# layer4.net
KiCad netlist of a schematic drawn in EAGLE
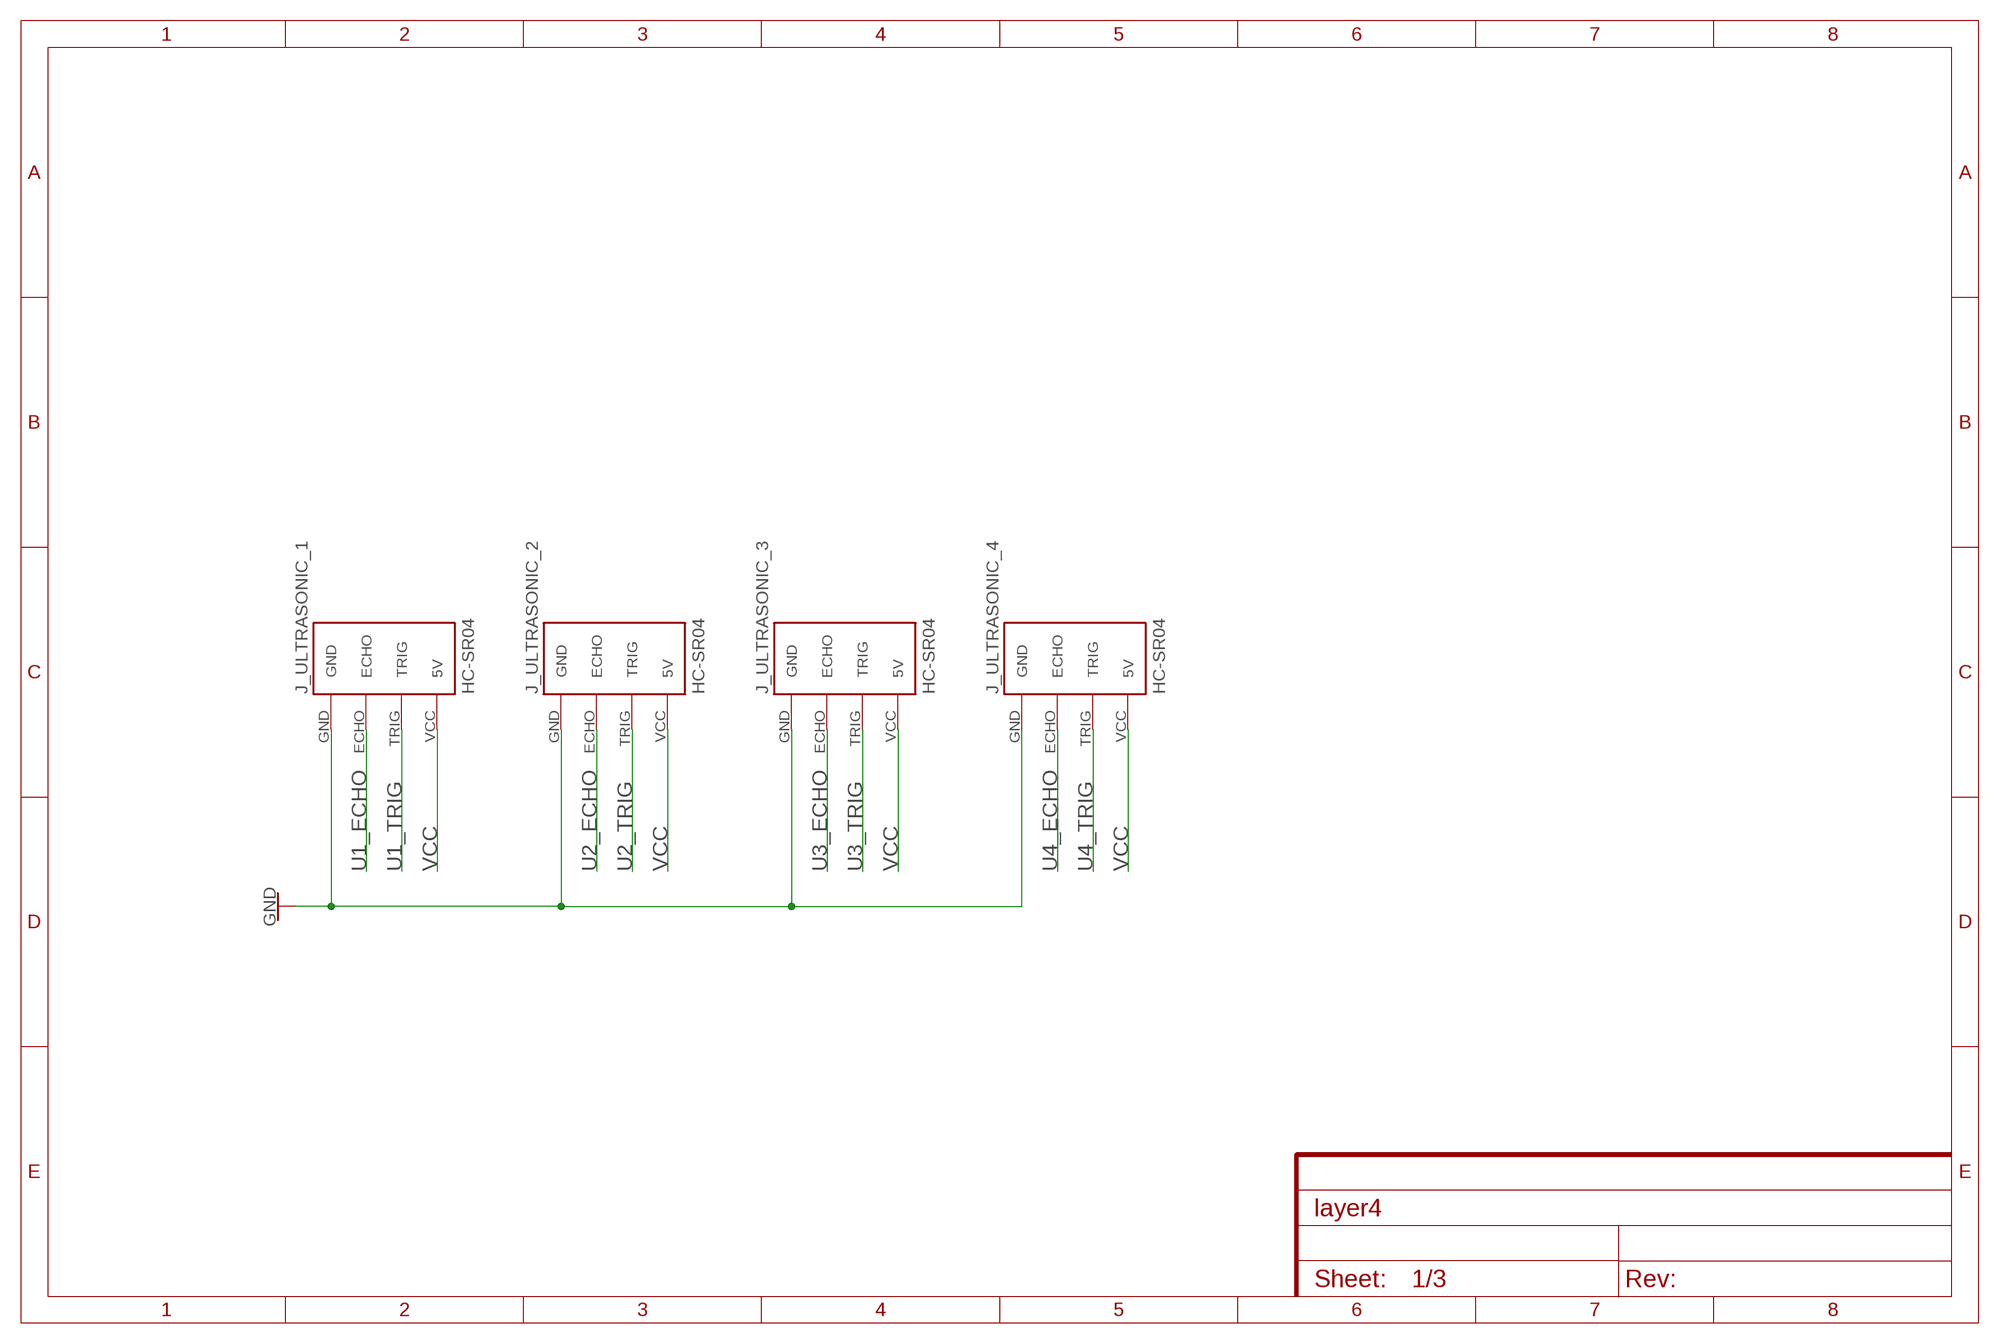
[diagram p0: schematic, sheet 1]
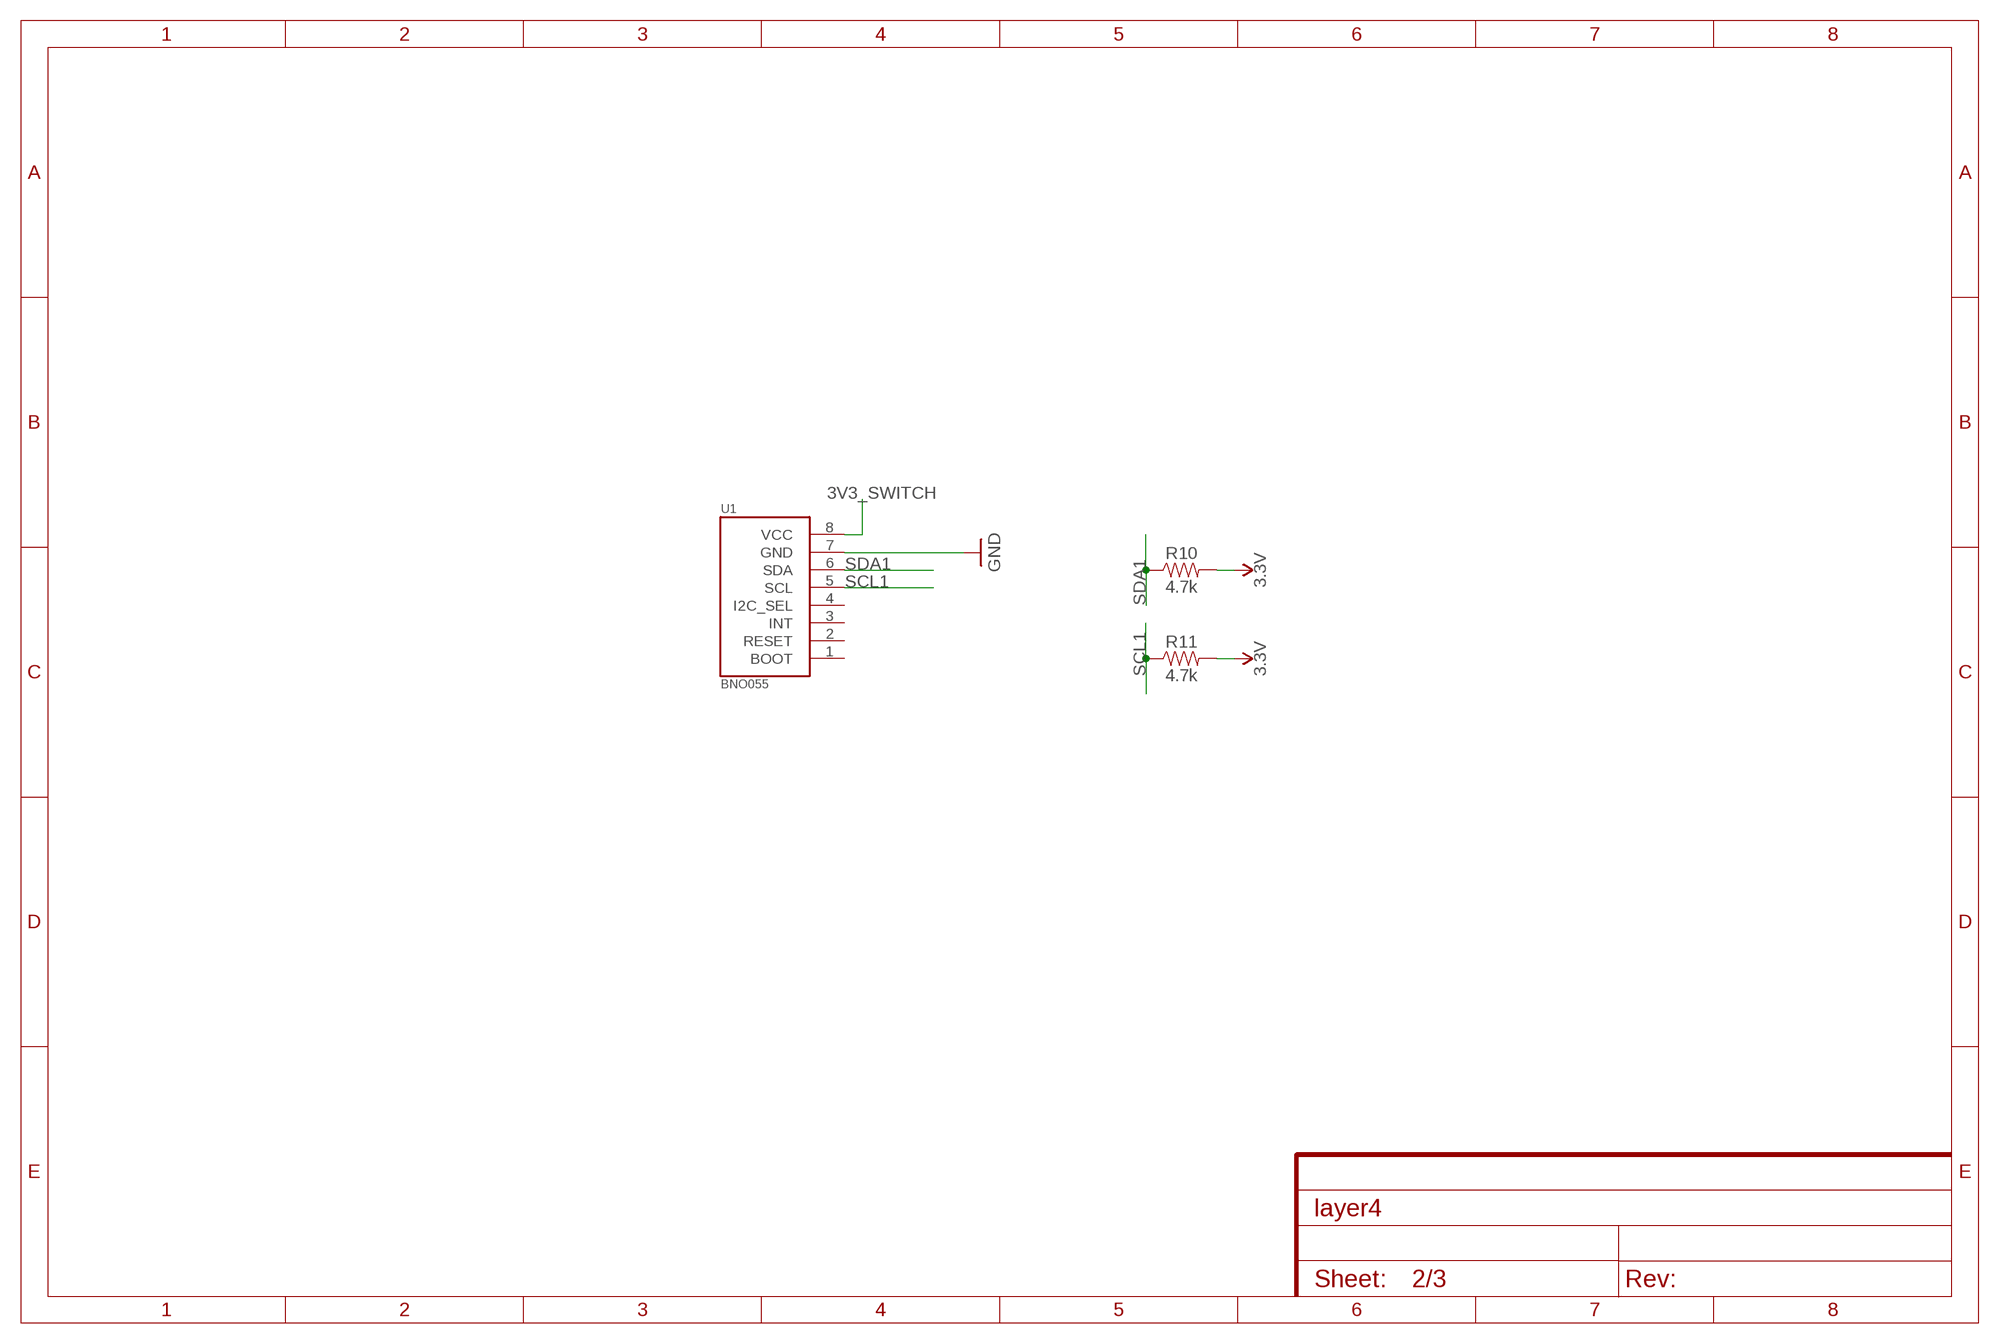
[diagram p1: schematic, sheet 2]
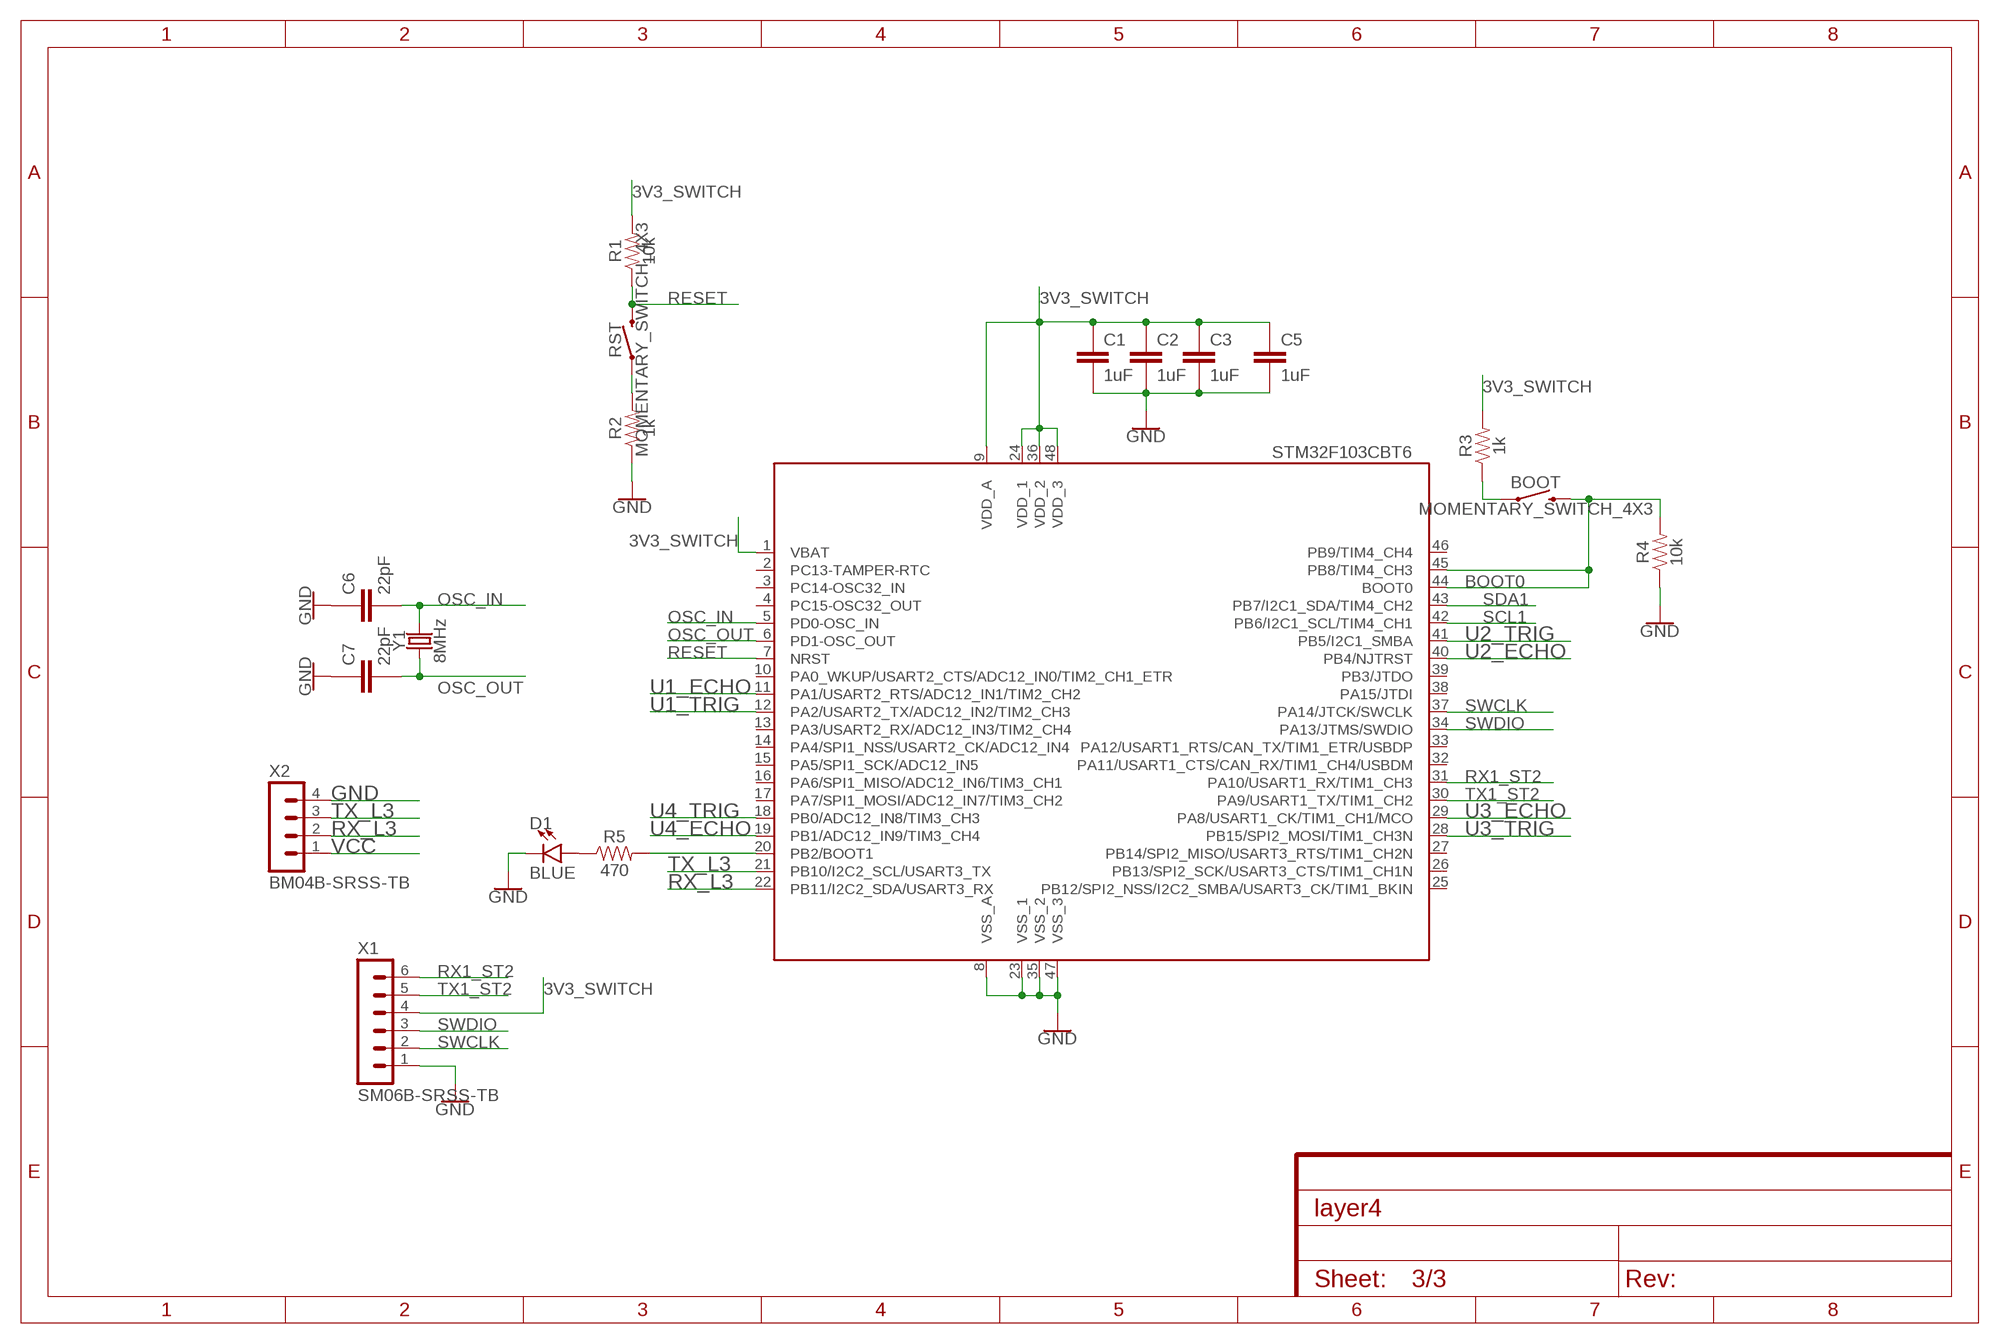
[diagram p2: schematic, sheet 3]

(export (version "E")
  (design (tool "Eeschema 10.0.6"))
  (components
    (comp (ref "BOOT")
      (value "MOMENTARY_SWITCH_4X3")
      (footprint "eagle-import:MOMENTARY_SWITCH_4X3")
      (libsource (lib "eagle-import") (part "MOMENTARY_SWITCH_4X3"))
    )
    (comp (ref "C1")
      (value "1uF")
      (footprint "eagle-import:C0603")
      (libsource (lib "eagle-import") (part "CAPACITOR0603"))
    )
    (comp (ref "C2")
      (value "1uF")
      (footprint "eagle-import:C0603")
      (libsource (lib "eagle-import") (part "CAPACITOR0603"))
    )
    (comp (ref "C3")
      (value "1uF")
      (footprint "eagle-import:C0603")
      (libsource (lib "eagle-import") (part "CAPACITOR0603"))
    )
    (comp (ref "C5")
      (value "1uF")
      (footprint "eagle-import:C0603")
      (libsource (lib "eagle-import") (part "CAPACITOR0603"))
    )
    (comp (ref "C6")
      (value "22pF")
      (footprint "eagle-import:C0603")
      (libsource (lib "eagle-import") (part "CAPACITOR0603"))
    )
    (comp (ref "C7")
      (value "22pF")
      (footprint "eagle-import:C0603")
      (libsource (lib "eagle-import") (part "CAPACITOR0603"))
    )
    (comp (ref "D1")
      (value "BLUE")
      (footprint "eagle-import:LED-0603")
      (libsource (lib "eagle-import") (part "LED0603"))
    )
    (comp (ref "R1")
      (value "10k")
      (footprint "eagle-import:R0603")
      (libsource (lib "eagle-import") (part "RESISTOR0603"))
    )
    (comp (ref "R2")
      (value "1k")
      (footprint "eagle-import:R0603")
      (libsource (lib "eagle-import") (part "RESISTOR0603"))
    )
    (comp (ref "R3")
      (value "1k")
      (footprint "eagle-import:R0603")
      (libsource (lib "eagle-import") (part "RESISTOR0603"))
    )
    (comp (ref "R4")
      (value "10k")
      (footprint "eagle-import:R0603")
      (libsource (lib "eagle-import") (part "RESISTOR0603"))
    )
    (comp (ref "R5")
      (value "470")
      (footprint "eagle-import:R0603")
      (libsource (lib "eagle-import") (part "RESISTOR0603"))
    )
    (comp (ref "RST")
      (value "MOMENTARY_SWITCH_4X3")
      (footprint "eagle-import:MOMENTARY_SWITCH_4X3")
      (libsource (lib "eagle-import") (part "MOMENTARY_SWITCH_4X3"))
    )
    (comp (ref "STM32_IR")
      (value "STM32F103CBT6")
      (footprint "eagle-import:LQFP48")
      (libsource (lib "eagle-import") (part "STM32F103CBT6"))
    )
    (comp (ref "X1")
      (value "SM06B-SRSS-TB")
      (footprint "eagle-import:SM06B-SRSS-TB")
      (libsource (lib "eagle-import") (part "SM06B-SRSS-TB"))
    )
    (comp (ref "X2")
      (value "BM04B-SRSS-TB")
      (footprint "eagle-import:BM04B-SRSS-TB")
      (libsource (lib "eagle-import") (part "BM04B-SRSS-TB"))
    )
    (comp (ref "Y1")
      (value "8MHz")
      (footprint "eagle-import:CRYSTAL-SMD-5X3.2-2PAD")
      (libsource (lib "eagle-import") (part "CRYSTALSMD-5X3.2-2PAD"))
    )
    (comp (ref "R10")
      (value "4.7k")
      (footprint "eagle-import:0603")
      (libsource (lib "eagle-import") (part "4.7KOHM-0603-1/10W-1%"))
    )
    (comp (ref "R11")
      (value "4.7k")
      (footprint "eagle-import:0603")
      (libsource (lib "eagle-import") (part "4.7KOHM-0603-1/10W-1%"))
    )
    (comp (ref "U1")
      (value "BNO055")
      (footprint "eagle-import:BNO055")
      (libsource (lib "eagle-import") (part "BNO055"))
    )
    (comp (ref "J_ULTRASONIC_1")
      (value "HC-SR04")
      (footprint "eagle-import:HC-SR04_FOOTPRINT")
      (libsource (lib "eagle-import") (part "HC-SR04"))
    )
    (comp (ref "J_ULTRASONIC_2")
      (value "HC-SR04")
      (footprint "eagle-import:HC-SR04_FOOTPRINT")
      (libsource (lib "eagle-import") (part "HC-SR04"))
    )
    (comp (ref "J_ULTRASONIC_3")
      (value "HC-SR04")
      (footprint "eagle-import:HC-SR04_FOOTPRINT")
      (libsource (lib "eagle-import") (part "HC-SR04"))
    )
    (comp (ref "J_ULTRASONIC_4")
      (value "HC-SR04")
      (footprint "eagle-import:HC-SR04_FOOTPRINT")
      (libsource (lib "eagle-import") (part "HC-SR04"))
    )
  )
  (nets
    (net (code "1") (name "3.3V") (class "Default")
      (node (ref "R10") (pin "2") (pinfunction "2_2") (pintype "passive"))
      (node (ref "R11") (pin "2") (pinfunction "2_2") (pintype "passive"))
    )
    (net (code "2") (name "3V3_SWITCH") (class "Default")
      (node (ref "C1") (pin "1") (pinfunction "1_1") (pintype "passive"))
      (node (ref "C2") (pin "1") (pinfunction "1_1") (pintype "passive"))
      (node (ref "C3") (pin "1") (pinfunction "1_1") (pintype "passive"))
      (node (ref "C5") (pin "2") (pinfunction "2_2") (pintype "passive"))
      (node (ref "R1") (pin "2") (pinfunction "2_2") (pintype "passive"))
      (node (ref "R3") (pin "2") (pinfunction "2_2") (pintype "passive"))
      (node (ref "STM32_IR") (pin "1") (pinfunction "VBAT_1") (pintype "power_in"))
      (node (ref "STM32_IR") (pin "24") (pinfunction "VDD_1_24") (pintype "power_in"))
      (node (ref "STM32_IR") (pin "36") (pinfunction "VDD_2_36") (pintype "power_in"))
      (node (ref "STM32_IR") (pin "48") (pinfunction "VDD_3_48") (pintype "power_in"))
      (node (ref "STM32_IR") (pin "9") (pinfunction "VDD_A_9") (pintype "power_in"))
      (node (ref "U1") (pin "8") (pinfunction "VCC_8") (pintype "bidirectional"))
      (node (ref "X1") (pin "4") (pinfunction "4_4") (pintype "passive"))
    )
    (net (code "3") (name "BOOT0") (class "Default")
      (node (ref "BOOT") (pin "P$2") (pinfunction "2_P$2") (pintype "passive"))
      (node (ref "R4") (pin "2") (pinfunction "2_2") (pintype "passive"))
      (node (ref "STM32_IR") (pin "44") (pinfunction "BOOT0_44") (pintype "input"))
      (node (ref "STM32_IR") (pin "45") (pinfunction "PB8/TIM4_CH3_45") (pintype "bidirectional"))
    )
    (net (code "4") (name "GND") (class "Default")
      (node (ref "C1") (pin "2") (pinfunction "2_2") (pintype "passive"))
      (node (ref "C2") (pin "2") (pinfunction "2_2") (pintype "passive"))
      (node (ref "C3") (pin "2") (pinfunction "2_2") (pintype "passive"))
      (node (ref "C5") (pin "1") (pinfunction "1_1") (pintype "passive"))
      (node (ref "C6") (pin "1") (pinfunction "1_1") (pintype "passive"))
      (node (ref "C7") (pin "1") (pinfunction "1_1") (pintype "passive"))
      (node (ref "D1") (pin "C") (pinfunction "C_C") (pintype "passive"))
      (node (ref "J_ULTRASONIC_1") (pin "GND") (pinfunction "GND_GND") (pintype "bidirectional"))
      (node (ref "J_ULTRASONIC_2") (pin "GND") (pinfunction "GND_GND") (pintype "bidirectional"))
      (node (ref "J_ULTRASONIC_3") (pin "GND") (pinfunction "GND_GND") (pintype "bidirectional"))
      (node (ref "J_ULTRASONIC_4") (pin "GND") (pinfunction "GND_GND") (pintype "bidirectional"))
      (node (ref "R2") (pin "1") (pinfunction "1_1") (pintype "passive"))
      (node (ref "R4") (pin "1") (pinfunction "1_1") (pintype "passive"))
      (node (ref "STM32_IR") (pin "23") (pinfunction "VSS_1_23") (pintype "power_in"))
      (node (ref "STM32_IR") (pin "35") (pinfunction "VSS_2_35") (pintype "power_in"))
      (node (ref "STM32_IR") (pin "47") (pinfunction "VSS_3_47") (pintype "power_in"))
      (node (ref "STM32_IR") (pin "8") (pinfunction "VSS_A_8") (pintype "power_in"))
      (node (ref "U1") (pin "7") (pinfunction "GND_7") (pintype "bidirectional"))
      (node (ref "X1") (pin "1") (pinfunction "1_1") (pintype "passive"))
      (node (ref "X2") (pin "4") (pinfunction "4_4") (pintype "passive"))
    )
    (net (code "5") (name "Net-(BOOT-1)") (class "Default")
      (node (ref "BOOT") (pin "P$1") (pinfunction "1_P$1") (pintype "passive"))
      (node (ref "R3") (pin "1") (pinfunction "1_1") (pintype "passive"))
    )
    (net (code "6") (name "Net-(D1-PadA)") (class "Default")
      (node (ref "D1") (pin "A") (pinfunction "A_A") (pintype "passive"))
      (node (ref "R5") (pin "1") (pinfunction "1_1") (pintype "passive"))
    )
    (net (code "7") (name "Net-(RST-1)") (class "Default")
      (node (ref "R2") (pin "2") (pinfunction "2_2") (pintype "passive"))
      (node (ref "RST") (pin "P$1") (pinfunction "1_P$1") (pintype "passive"))
    )
    (net (code "8") (name "Net-(STM32_IR-PB2{slash}BOOT1)") (class "Default")
      (node (ref "R5") (pin "2") (pinfunction "2_2") (pintype "passive"))
      (node (ref "STM32_IR") (pin "20") (pinfunction "PB2/BOOT1_20") (pintype "bidirectional"))
    )
    (net (code "9") (name "OSC_IN") (class "Default")
      (node (ref "C6") (pin "2") (pinfunction "2_2") (pintype "passive"))
      (node (ref "STM32_IR") (pin "5") (pinfunction "PD0-OSC_IN_5") (pintype "input"))
      (node (ref "Y1") (pin "P$2") (pinfunction "2_P$2") (pintype "passive"))
    )
    (net (code "10") (name "OSC_OUT") (class "Default")
      (node (ref "C7") (pin "2") (pinfunction "2_2") (pintype "passive"))
      (node (ref "STM32_IR") (pin "6") (pinfunction "PD1-OSC_OUT_6") (pintype "input"))
      (node (ref "Y1") (pin "P$1") (pinfunction "1_P$1") (pintype "passive"))
    )
    (net (code "11") (name "RESET") (class "Default")
      (node (ref "R1") (pin "1") (pinfunction "1_1") (pintype "passive"))
      (node (ref "RST") (pin "P$2") (pinfunction "2_P$2") (pintype "passive"))
      (node (ref "STM32_IR") (pin "7") (pinfunction "NRST_7") (pintype "input"))
    )
    (net (code "12") (name "RX1_ST2") (class "Default")
      (node (ref "STM32_IR") (pin "31") (pinfunction "PA10/USART1_RX/TIM1_CH3_31") (pintype "bidirectional"))
      (node (ref "X1") (pin "6") (pinfunction "6_6") (pintype "passive"))
    )
    (net (code "13") (name "RX_L3") (class "Default")
      (node (ref "STM32_IR") (pin "22") (pinfunction "PB11/I2C2_SDA/USART3_RX_22") (pintype "input"))
      (node (ref "X2") (pin "2") (pinfunction "2_2") (pintype "passive"))
    )
    (net (code "14") (name "SCL1") (class "Default")
      (node (ref "R11") (pin "1") (pinfunction "1_1") (pintype "passive"))
      (node (ref "STM32_IR") (pin "42") (pinfunction "PB6/I2C1_SCL/TIM4_CH1_42") (pintype "input"))
      (node (ref "U1") (pin "5") (pinfunction "SCL_5") (pintype "bidirectional"))
    )
    (net (code "15") (name "SDA1") (class "Default")
      (node (ref "R10") (pin "1") (pinfunction "1_1") (pintype "passive"))
      (node (ref "STM32_IR") (pin "43") (pinfunction "PB7/I2C1_SDA/TIM4_CH2_43") (pintype "bidirectional"))
      (node (ref "U1") (pin "6") (pinfunction "SDA_6") (pintype "bidirectional"))
    )
    (net (code "16") (name "SWCLK") (class "Default")
      (node (ref "STM32_IR") (pin "37") (pinfunction "PA14/JTCK/SWCLK_37") (pintype "bidirectional"))
      (node (ref "X1") (pin "2") (pinfunction "2_2") (pintype "passive"))
    )
    (net (code "17") (name "SWDIO") (class "Default")
      (node (ref "STM32_IR") (pin "34") (pinfunction "PA13/JTMS/SWDIO_34") (pintype "bidirectional"))
      (node (ref "X1") (pin "3") (pinfunction "3_3") (pintype "passive"))
    )
    (net (code "18") (name "TX1_ST2") (class "Default")
      (node (ref "STM32_IR") (pin "30") (pinfunction "PA9/USART1_TX/TIM1_CH2_30") (pintype "input"))
      (node (ref "X1") (pin "5") (pinfunction "5_5") (pintype "passive"))
    )
    (net (code "19") (name "TX_L3") (class "Default")
      (node (ref "STM32_IR") (pin "21") (pinfunction "PB10/I2C2_SCL/USART3_TX_21") (pintype "input"))
      (node (ref "X2") (pin "3") (pinfunction "3_3") (pintype "passive"))
    )
    (net (code "20") (name "U1_ECHO") (class "Default")
      (node (ref "J_ULTRASONIC_1") (pin "ECHO") (pinfunction "ECHO_ECHO") (pintype "bidirectional"))
      (node (ref "STM32_IR") (pin "11") (pinfunction "PA1/USART2_RTS/ADC12_IN1/TIM2_CH2_11") (pintype "bidirectional"))
    )
    (net (code "21") (name "U1_TRIG") (class "Default")
      (node (ref "J_ULTRASONIC_1") (pin "TRIG") (pinfunction "TRIG_TRIG") (pintype "bidirectional"))
      (node (ref "STM32_IR") (pin "12") (pinfunction "PA2/USART2_TX/ADC12_IN2/TIM2_CH3_12") (pintype "bidirectional"))
    )
    (net (code "22") (name "U2_ECHO") (class "Default")
      (node (ref "J_ULTRASONIC_2") (pin "ECHO") (pinfunction "ECHO_ECHO") (pintype "bidirectional"))
      (node (ref "STM32_IR") (pin "40") (pinfunction "PB4/NJTRST_40") (pintype "bidirectional"))
    )
    (net (code "23") (name "U2_TRIG") (class "Default")
      (node (ref "J_ULTRASONIC_2") (pin "TRIG") (pinfunction "TRIG_TRIG") (pintype "bidirectional"))
      (node (ref "STM32_IR") (pin "41") (pinfunction "PB5/I2C1_SMBA_41") (pintype "input"))
    )
    (net (code "24") (name "U3_ECHO") (class "Default")
      (node (ref "J_ULTRASONIC_3") (pin "ECHO") (pinfunction "ECHO_ECHO") (pintype "bidirectional"))
      (node (ref "STM32_IR") (pin "29") (pinfunction "PA8/USART1_CK/TIM1_CH1/MCO_29") (pintype "bidirectional"))
    )
    (net (code "25") (name "U3_TRIG") (class "Default")
      (node (ref "J_ULTRASONIC_3") (pin "TRIG") (pinfunction "TRIG_TRIG") (pintype "bidirectional"))
      (node (ref "STM32_IR") (pin "28") (pinfunction "PB15/SPI2_MOSI/TIM1_CH3N_28") (pintype "input"))
    )
    (net (code "26") (name "U4_ECHO") (class "Default")
      (node (ref "J_ULTRASONIC_4") (pin "ECHO") (pinfunction "ECHO_ECHO") (pintype "bidirectional"))
      (node (ref "STM32_IR") (pin "19") (pinfunction "PB1/ADC12_IN9/TIM3_CH4_19") (pintype "bidirectional"))
    )
    (net (code "27") (name "U4_TRIG") (class "Default")
      (node (ref "J_ULTRASONIC_4") (pin "TRIG") (pinfunction "TRIG_TRIG") (pintype "bidirectional"))
      (node (ref "STM32_IR") (pin "18") (pinfunction "PB0/ADC12_IN8/TIM3_CH3_18") (pintype "bidirectional"))
    )
    (net (code "28") (name "VCC") (class "Default")
      (node (ref "J_ULTRASONIC_1") (pin "VCC") (pinfunction "5V_VCC") (pintype "bidirectional"))
      (node (ref "J_ULTRASONIC_2") (pin "VCC") (pinfunction "5V_VCC") (pintype "bidirectional"))
      (node (ref "J_ULTRASONIC_3") (pin "VCC") (pinfunction "5V_VCC") (pintype "bidirectional"))
      (node (ref "J_ULTRASONIC_4") (pin "VCC") (pinfunction "5V_VCC") (pintype "bidirectional"))
      (node (ref "X2") (pin "1") (pinfunction "1_1") (pintype "passive"))
    )
    (net (code "29") (name "unconnected-(STM32_IR-PA0_WKUP{slash}USART2_CTS{slash}ADC12_IN0{slash}TIM2_CH1_ETR-Pad10)") (class "Default")
      (node (ref "STM32_IR") (pin "10") (pinfunction "PA0_WKUP/USART2_CTS/ADC12_IN0/TIM2_CH1_ETR_10") (pintype "bidirectional"))
    )
    (net (code "30") (name "unconnected-(STM32_IR-PA3{slash}USART2_RX{slash}ADC12_IN3{slash}TIM2_CH4-Pad13)") (class "Default")
      (node (ref "STM32_IR") (pin "13") (pinfunction "PA3/USART2_RX/ADC12_IN3/TIM2_CH4_13") (pintype "bidirectional"))
    )
    (net (code "31") (name "unconnected-(STM32_IR-PA4{slash}SPI1_NSS{slash}USART2_CK{slash}ADC12_IN4-Pad14)") (class "Default")
      (node (ref "STM32_IR") (pin "14") (pinfunction "PA4/SPI1_NSS/USART2_CK/ADC12_IN4_14") (pintype "bidirectional"))
    )
    (net (code "32") (name "unconnected-(STM32_IR-PA5{slash}SPI1_SCK{slash}ADC12_IN5-Pad15)") (class "Default")
      (node (ref "STM32_IR") (pin "15") (pinfunction "PA5/SPI1_SCK/ADC12_IN5_15") (pintype "bidirectional"))
    )
    (net (code "33") (name "unconnected-(STM32_IR-PA6{slash}SPI1_MISO{slash}ADC12_IN6{slash}TIM3_CH1-Pad16)") (class "Default")
      (node (ref "STM32_IR") (pin "16") (pinfunction "PA6/SPI1_MISO/ADC12_IN6/TIM3_CH1_16") (pintype "bidirectional"))
    )
    (net (code "34") (name "unconnected-(STM32_IR-PA7{slash}SPI1_MOSI{slash}ADC12_IN7{slash}TIM3_CH2-Pad17)") (class "Default")
      (node (ref "STM32_IR") (pin "17") (pinfunction "PA7/SPI1_MOSI/ADC12_IN7/TIM3_CH2_17") (pintype "bidirectional"))
    )
    (net (code "35") (name "unconnected-(STM32_IR-PA11{slash}USART1_CTS{slash}CAN_RX{slash}TIM1_CH4{slash}USBDM-Pad32)") (class "Default")
      (node (ref "STM32_IR") (pin "32") (pinfunction "PA11/USART1_CTS/CAN_RX/TIM1_CH4/USBDM_32") (pintype "bidirectional"))
    )
    (net (code "36") (name "unconnected-(STM32_IR-PA12{slash}USART1_RTS{slash}CAN_TX{slash}TIM1_ETR{slash}USBDP-Pad33)") (class "Default")
      (node (ref "STM32_IR") (pin "33") (pinfunction "PA12/USART1_RTS/CAN_TX/TIM1_ETR/USBDP_33") (pintype "bidirectional"))
    )
    (net (code "37") (name "unconnected-(STM32_IR-PA15{slash}JTDI-Pad38)") (class "Default")
      (node (ref "STM32_IR") (pin "38") (pinfunction "PA15/JTDI_38") (pintype "bidirectional"))
    )
    (net (code "38") (name "unconnected-(STM32_IR-PB3{slash}JTDO-Pad39)") (class "Default")
      (node (ref "STM32_IR") (pin "39") (pinfunction "PB3/JTDO_39") (pintype "bidirectional"))
    )
    (net (code "39") (name "unconnected-(STM32_IR-PB9{slash}TIM4_CH4-Pad46)") (class "Default")
      (node (ref "STM32_IR") (pin "46") (pinfunction "PB9/TIM4_CH4_46") (pintype "input"))
    )
    (net (code "40") (name "unconnected-(STM32_IR-PB12{slash}SPI2_NSS{slash}I2C2_SMBA{slash}USART3_CK{slash}TIM1_BKIN-Pad25)") (class "Default")
      (node (ref "STM32_IR") (pin "25") (pinfunction "PB12/SPI2_NSS/I2C2_SMBA/USART3_CK/TIM1_BKIN_25") (pintype "input"))
    )
    (net (code "41") (name "unconnected-(STM32_IR-PB13{slash}SPI2_SCK{slash}USART3_CTS{slash}TIM1_CH1N-Pad26)") (class "Default")
      (node (ref "STM32_IR") (pin "26") (pinfunction "PB13/SPI2_SCK/USART3_CTS/TIM1_CH1N_26") (pintype "input"))
    )
    (net (code "42") (name "unconnected-(STM32_IR-PB14{slash}SPI2_MISO{slash}USART3_RTS{slash}TIM1_CH2N-Pad27)") (class "Default")
      (node (ref "STM32_IR") (pin "27") (pinfunction "PB14/SPI2_MISO/USART3_RTS/TIM1_CH2N_27") (pintype "input"))
    )
    (net (code "43") (name "unconnected-(STM32_IR-PC13-TAMPER-RTC-Pad2)") (class "Default")
      (node (ref "STM32_IR") (pin "2") (pinfunction "PC13-TAMPER-RTC_2") (pintype "input"))
    )
    (net (code "44") (name "unconnected-(STM32_IR-PC14-OSC32_IN-Pad3)") (class "Default")
      (node (ref "STM32_IR") (pin "3") (pinfunction "PC14-OSC32_IN_3") (pintype "input"))
    )
    (net (code "45") (name "unconnected-(STM32_IR-PC15-OSC32_OUT-Pad4)") (class "Default")
      (node (ref "STM32_IR") (pin "4") (pinfunction "PC15-OSC32_OUT_4") (pintype "input"))
    )
    (net (code "46") (name "unconnected-(U1-BOOT-Pad1)") (class "Default")
      (node (ref "U1") (pin "1") (pinfunction "BOOT_1") (pintype "bidirectional"))
    )
    (net (code "47") (name "unconnected-(U1-I2C_SEL-Pad4)") (class "Default")
      (node (ref "U1") (pin "4") (pinfunction "I2C_SEL_4") (pintype "bidirectional"))
    )
    (net (code "48") (name "unconnected-(U1-INT-Pad3)") (class "Default")
      (node (ref "U1") (pin "3") (pinfunction "INT_3") (pintype "bidirectional"))
    )
    (net (code "49") (name "unconnected-(U1-RESET-Pad2)") (class "Default")
      (node (ref "U1") (pin "2") (pinfunction "RESET_2") (pintype "bidirectional"))
    )
  )
)
